# Main.net
KiCad netlist of a schematic drawn in Altium Designer
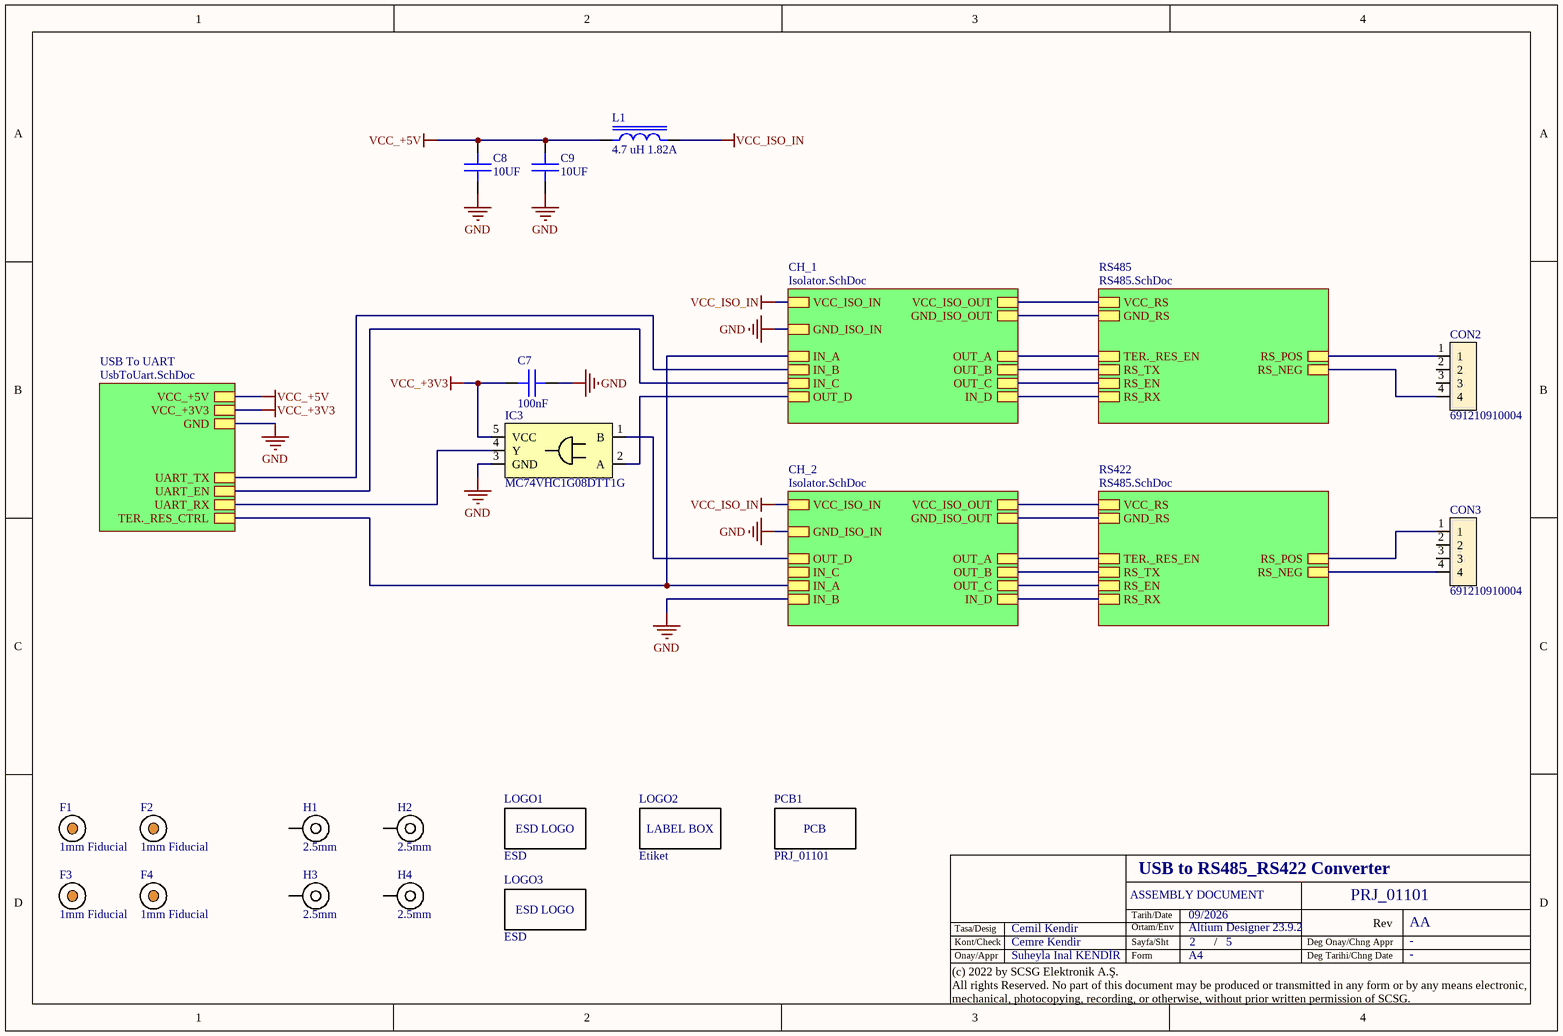
[diagram p0: Main.SchDoc]

(export (version "E")
  (design (tool "Eeschema 10.0.6"))
  (components
    (comp (ref "C7")
      (value "100nF")
      (footprint "C0603")
      (description "100nF, 25V, X7R, 0603")
      (fields
        (field (name "MANUFACTURER") "Yageo")
        (field (name "MANUFACTURER PART NUMBER") "CC0603KRX7R8BB104")
      )
      (libsource (lib "Capacitor") (part "CC0603KRX7R8BB104"))
    )
    (comp (ref "C8")
      (value "10UF")
      (footprint "c1206")
      (description "10UF, 16V, X7R, 1206")
      (fields
        (field (name "MANUFACTURER") "Samsung")
        (field (name "MANUFACTURER PART NUMBER") "CL31B106MOHNNNE")
      )
      (libsource (lib "Capacitor") (part "CL31B106MOHNNNE"))
    )
    (comp (ref "C9")
      (value "10UF")
      (footprint "c1206")
      (description "10UF, 16V, X7R, 1206")
      (fields
        (field (name "MANUFACTURER") "Samsung")
        (field (name "MANUFACTURER PART NUMBER") "CL31B106MOHNNNE")
      )
      (libsource (lib "Capacitor") (part "CL31B106MOHNNNE"))
    )
    (comp (ref "CON2")
      (value "691210910004")
      (footprint "691210910004")
      (description "WR-TBL Terminal block - Rising Cage - THT")
      (fields (field (name "MANUFACTURER") "Wurth Elektronik"))
      (libsource (lib "Connectors") (part "691210910004"))
    )
    (comp (ref "CON3")
      (value "691210910004")
      (footprint "691210910004")
      (description "WR-TBL Terminal block - Rising Cage - THT")
      (fields (field (name "MANUFACTURER") "Wurth Elektronik"))
      (libsource (lib "Connectors") (part "691210910004"))
    )
    (comp (ref "F1")
      (value "1mm Fiducial")
      (footprint "1mm Fiducial")
      (fields (field (name "MANUFACTURER") "--") (field (name "MANUFACTURER PART NUMBER") "Fiducial 2mm"))
      (libsource (lib "Mechanical") (part "1mm Fiducial"))
    )
    (comp (ref "F2")
      (value "1mm Fiducial")
      (footprint "1mm Fiducial")
      (fields (field (name "MANUFACTURER") "--") (field (name "MANUFACTURER PART NUMBER") "Fiducial 2mm"))
      (libsource (lib "Mechanical") (part "1mm Fiducial"))
    )
    (comp (ref "F3")
      (value "1mm Fiducial")
      (footprint "1mm Fiducial")
      (fields (field (name "MANUFACTURER") "--") (field (name "MANUFACTURER PART NUMBER") "Fiducial 2mm"))
      (libsource (lib "Mechanical") (part "1mm Fiducial"))
    )
    (comp (ref "F4")
      (value "1mm Fiducial")
      (footprint "1mm Fiducial")
      (fields (field (name "MANUFACTURER") "--") (field (name "MANUFACTURER PART NUMBER") "Fiducial 2mm"))
      (libsource (lib "Mechanical") (part "1mm Fiducial"))
    )
    (comp (ref "H1")
      (value "2.5mm")
      (footprint "2.5mm hole")
      (description "2.5mm hole")
      (fields (field (name "MANUFACTURER") "--"))
      (libsource (lib "Mechanical") (part "2.5 mm Hole"))
    )
    (comp (ref "H2")
      (value "2.5mm")
      (footprint "2.5mm hole")
      (description "2.5mm hole")
      (fields (field (name "MANUFACTURER") "--"))
      (libsource (lib "Mechanical") (part "2.5 mm Hole"))
    )
    (comp (ref "H3")
      (value "2.5mm")
      (footprint "2.5mm hole")
      (description "2.5mm hole")
      (fields (field (name "MANUFACTURER") "--"))
      (libsource (lib "Mechanical") (part "2.5 mm Hole"))
    )
    (comp (ref "H4")
      (value "2.5mm")
      (footprint "2.5mm hole")
      (description "2.5mm hole")
      (fields (field (name "MANUFACTURER") "--"))
      (libsource (lib "Mechanical") (part "2.5 mm Hole"))
    )
    (comp (ref "IC3")
      (value "MC74VHC1G08DTT1G")
      (footprint "SOT23-5")
      (description "MC74VHC1G08 Series 2 to 5.5 SMT Single 2 Input AND Gate - SOT-23-5")
      (fields (field (name "MANUFACTURER") "ON Semiconductor"))
      (libsource (lib "IntegratedCircuit") (part "MC74VHC1G08DTT1G"))
    )
    (comp (ref "L1")
      (value "4.7 uH 1.82A")
      (footprint "WE-PD2_4532")
      (description "WE-PD2, Unshielded Wire-wound SMD Inductor With Ferrite Core, 4.7 Uh, 1.82A I")
      (fields
        (field (name "MANUFACTURER") "Wurth Elektronik")
        (field (name "MANUFACTURER PART NUMBER") "744773047")
      )
      (libsource (lib "Inductor") (part "744773047"))
    )
    (comp (ref "LOGO1")
      (value "ESD")
      (footprint "ESD")
      (description "ESD LOGO")
      (fields (field (name "MANUFACTURER") "--"))
      (libsource (lib "Mechanical") (part "ESD"))
    )
    (comp (ref "LOGO2")
      (value "Etiket")
      (footprint "ETIKET")
      (description "Etiket kutu")
      (fields (field (name "MANUFACTURER") "--"))
      (libsource (lib "Mechanical") (part "Etiket"))
    )
    (comp (ref "LOGO3")
      (value "ESD")
      (footprint "ESD")
      (description "ESD LOGO")
      (fields (field (name "MANUFACTURER") "--"))
      (libsource (lib "Mechanical") (part "ESD"))
    )
    (comp (ref "PCB1")
      (value "~")
      (footprint "PCB")
      (description "PCB")
      (fields (field (name "MANUFACTURER") "CUSTOM"))
      (libsource (lib "Mechanical") (part "PCB"))
    )
  )
  (nets
    (net (code "15") (name "/OUT_D") (class "Default")
      (node (ref "IC3") (pin "1") (pinfunction "B_1") (pintype "passive"))
    )
    (net (code "16") (name "/OUT_D_1") (class "Default")
      (node (ref "IC3") (pin "2") (pinfunction "A_2") (pintype "passive"))
    )
    (net (code "17") (name "/RS_NEG") (class "Default")
      (node (ref "CON2") (pin "4") (pinfunction "4_4") (pintype "passive"))
    )
    (net (code "18") (name "/RS_NEG_1") (class "Default")
      (node (ref "CON3") (pin "4") (pinfunction "4_4") (pintype "passive"))
    )
    (net (code "19") (name "/RS_POS") (class "Default")
      (node (ref "CON2") (pin "1") (pinfunction "1_1") (pintype "passive"))
    )
    (net (code "20") (name "/RS_POS_1") (class "Default")
      (node (ref "CON3") (pin "1") (pinfunction "1_1") (pintype "passive"))
    )
    (net (code "21") (name "/UART_RX") (class "Default")
      (node (ref "IC3") (pin "4") (pinfunction "Y_4") (pintype "passive"))
    )
    (net (code "24") (name "GND") (class "Default")
      (node (ref "C7") (pin "1") (pintype "passive"))
      (node (ref "C8") (pin "1") (pintype "passive"))
      (node (ref "C9") (pin "1") (pintype "passive"))
      (node (ref "IC3") (pin "3") (pinfunction "GND_3") (pintype "passive"))
    )
    (net (code "25") (name "VCC_+3V3") (class "Default")
      (node (ref "C7") (pin "2") (pintype "passive"))
      (node (ref "IC3") (pin "5") (pinfunction "VCC_5") (pintype "passive"))
    )
    (net (code "26") (name "VCC_+5V") (class "Default")
      (node (ref "C8") (pin "2") (pintype "passive"))
      (node (ref "C9") (pin "2") (pintype "passive"))
      (node (ref "L1") (pin "1") (pinfunction "1_1") (pintype "passive"))
    )
    (net (code "27") (name "VCC_ISO_IN") (class "Default")
      (node (ref "L1") (pin "2") (pinfunction "2_2") (pintype "passive"))
    )
    (net (code "28") (name "unconnected-(CON2-Pad2)") (class "Default")
      (node (ref "CON2") (pin "2") (pinfunction "2_2") (pintype "passive"))
    )
    (net (code "29") (name "unconnected-(CON2-Pad3)") (class "Default")
      (node (ref "CON2") (pin "3") (pinfunction "3_3") (pintype "passive"))
    )
    (net (code "30") (name "unconnected-(CON3-Pad2)") (class "Default")
      (node (ref "CON3") (pin "2") (pinfunction "2_2") (pintype "passive"))
    )
    (net (code "31") (name "unconnected-(CON3-Pad3)") (class "Default")
      (node (ref "CON3") (pin "3") (pinfunction "3_3") (pintype "passive"))
    )
    (net (code "32") (name "unconnected-(H1-Pad1)") (class "Default")
      (node (ref "H1") (pin "1") (pinfunction "1_1") (pintype "passive"))
    )
    (net (code "33") (name "unconnected-(H2-Pad1)") (class "Default")
      (node (ref "H2") (pin "1") (pinfunction "1_1") (pintype "passive"))
    )
    (net (code "34") (name "unconnected-(H3-Pad1)") (class "Default")
      (node (ref "H3") (pin "1") (pinfunction "1_1") (pintype "passive"))
    )
    (net (code "35") (name "unconnected-(H4-Pad1)") (class "Default")
      (node (ref "H4") (pin "1") (pinfunction "1_1") (pintype "passive"))
    )
  )
)
